# Reset.net
KiCad netlist of a schematic drawn in Altium Designer
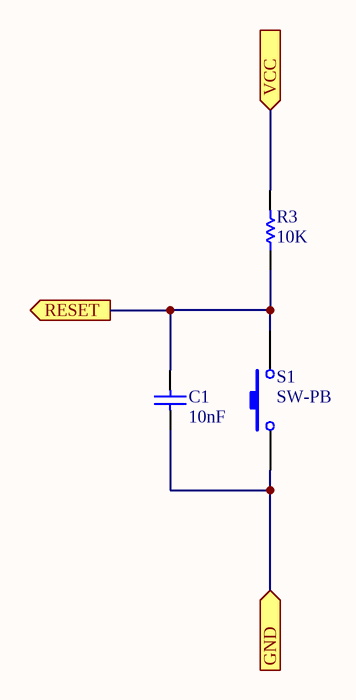
[diagram p0: Reset.SchDoc]

(export (version "E")
  (design (tool "Eeschema 10.0.6"))
  (components
    (comp (ref "C1")
      (value "10nF")
      (footprint "RAD-0.3")
      (description "Capacitor")
      (fields (field (name "PUBLISHER") "Altium Limited"))
      (libsource (lib "Miscellaneous Devices") (part "Cap"))
    )
    (comp (ref "R3")
      (value "10K")
      (footprint "AXIAL-0.3")
      (description "Resistor")
      (fields (field (name "PUBLISHER") "Altium Limited"))
      (libsource (lib "Miscellaneous Devices") (part "Res1"))
    )
    (comp (ref "S1")
      (value "SW-PB")
      (footprint "SPST-2")
      (description "Switch")
      (fields (field (name "PUBLISHER") "Altium Limited"))
      (libsource (lib "Miscellaneous Devices") (part "SW-PB"))
    )
  )
  (nets
    (net (code "1") (name "/GND") (class "Default")
      (node (ref "C1") (pin "1") (pinfunction "1_1") (pintype "passive"))
      (node (ref "S1") (pin "1") (pinfunction "1_1") (pintype "passive"))
    )
    (net (code "2") (name "/RESET") (class "Default")
      (node (ref "C1") (pin "2") (pinfunction "2_2") (pintype "passive"))
      (node (ref "R3") (pin "1") (pinfunction "1_1") (pintype "passive"))
      (node (ref "S1") (pin "2") (pinfunction "2_2") (pintype "passive"))
    )
    (net (code "3") (name "/VCC") (class "Default")
      (node (ref "R3") (pin "2") (pinfunction "2_2") (pintype "passive"))
    )
  )
)
